# wemos-d1-screw-terminal-v2_0.net
KiCad netlist of a schematic drawn in EAGLE
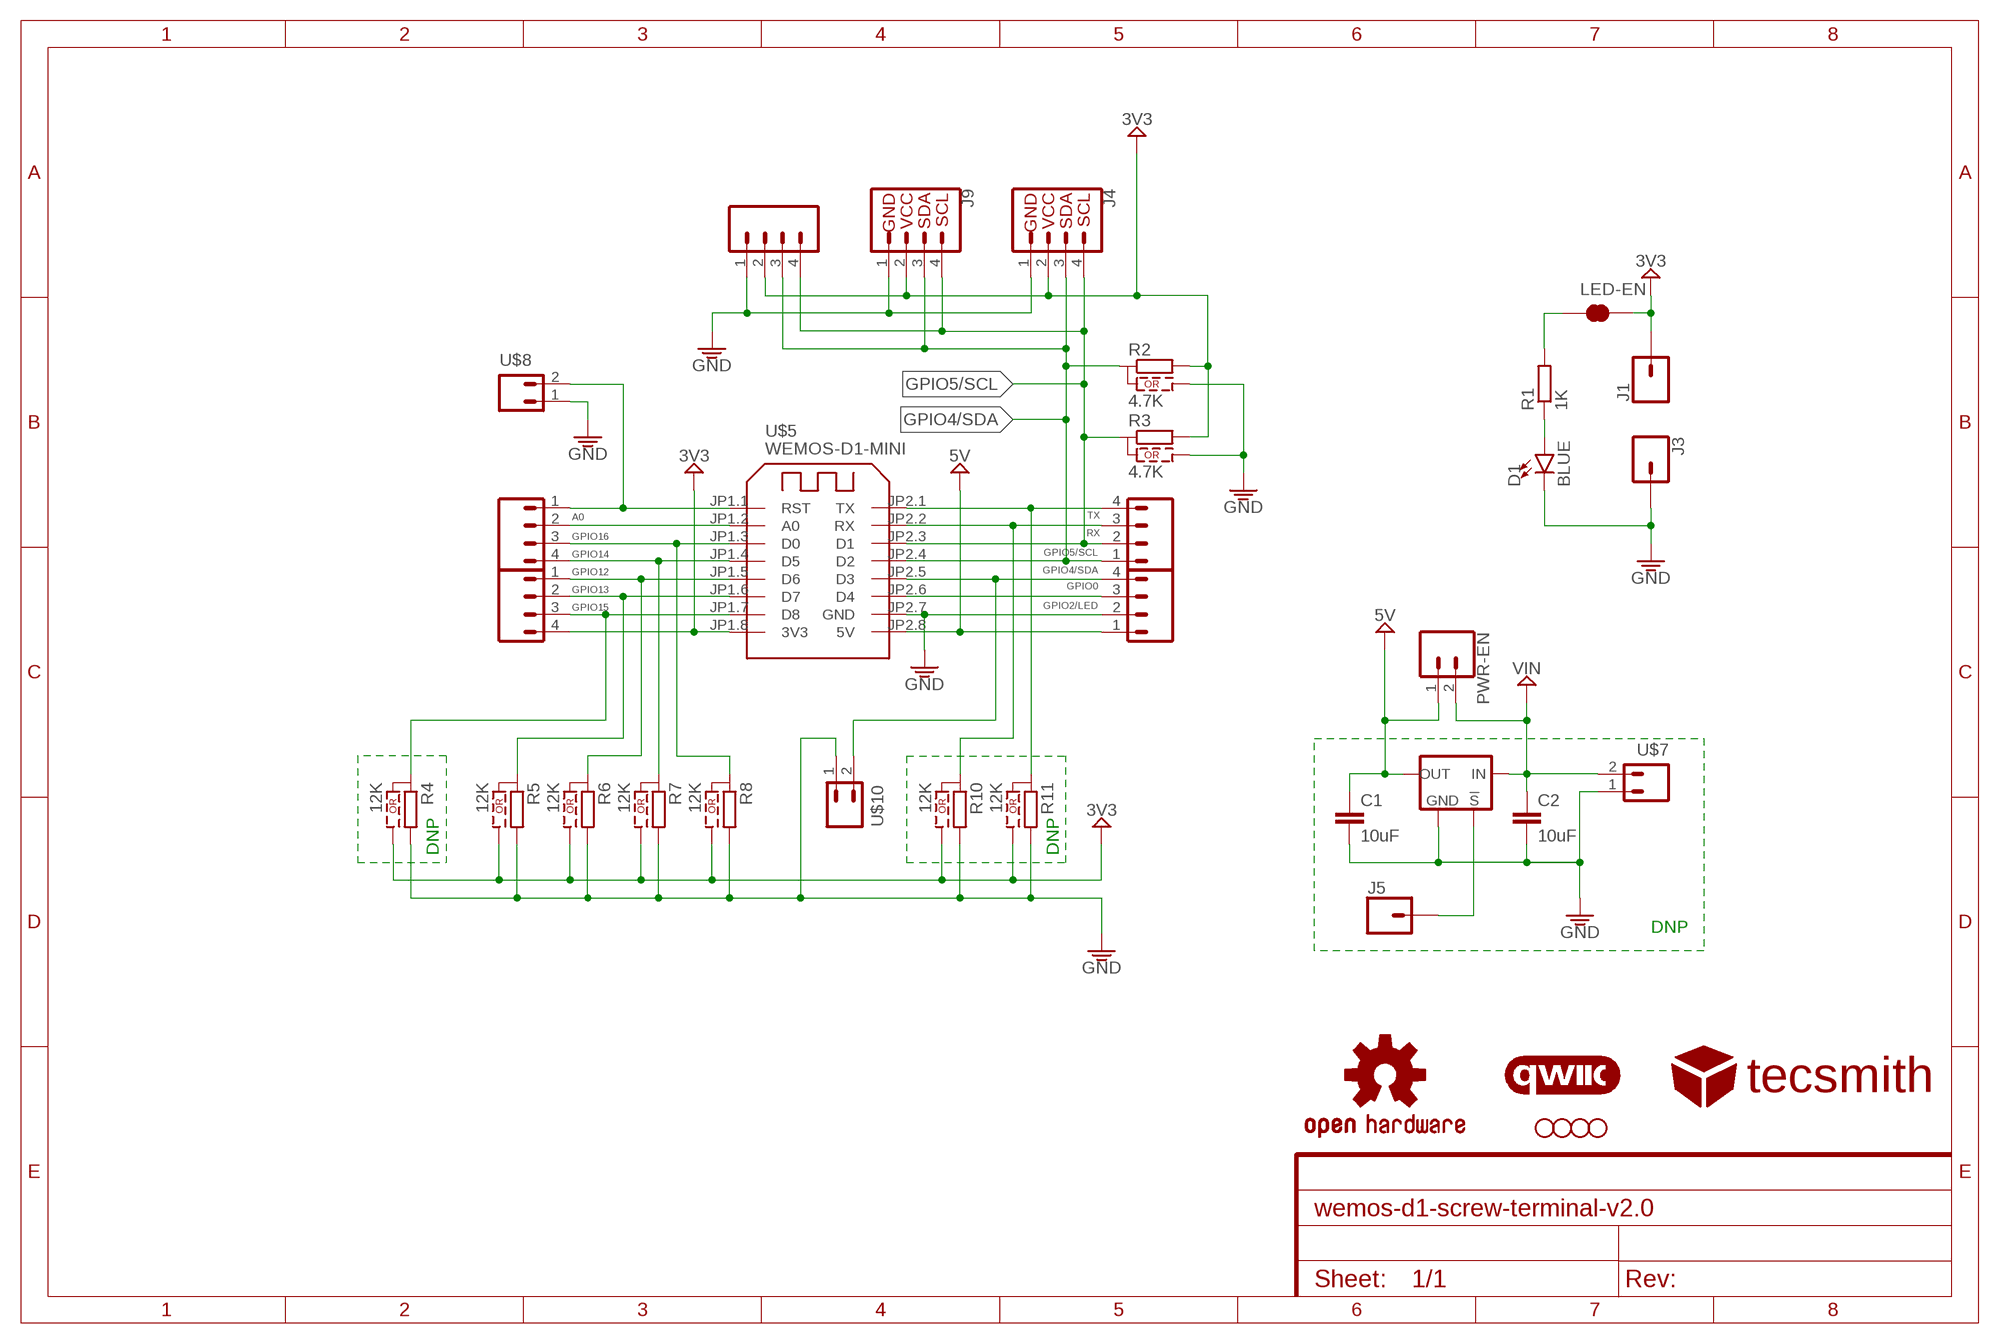
[diagram p0: schematic, sheet 1]

(export (version "E")
  (design (tool "Eeschema 10.0.6"))
  (components
    (comp (ref "C1")
      (value "10uF")
      (footprint "eagle-import:0805")
      (libsource (lib "eagle-import") (part "10UF-0805-10V-10%"))
    )
    (comp (ref "C2")
      (value "10uF")
      (footprint "eagle-import:0805")
      (libsource (lib "eagle-import") (part "10UF-0805-10V-10%"))
    )
    (comp (ref "D1")
      (value "BLUE")
      (footprint "eagle-import:LED-0603")
      (libsource (lib "eagle-import") (part "LED-BLUE0603"))
    )
    (comp (ref "H1")
      (value "STAND-OFF")
      (footprint "eagle-import:STAND-OFF")
      (libsource (lib "eagle-import") (part "STAND-OFF"))
    )
    (comp (ref "H2")
      (value "STAND-OFF")
      (footprint "eagle-import:STAND-OFF")
      (libsource (lib "eagle-import") (part "STAND-OFF"))
    )
    (comp (ref "H5")
      (value "STAND-OFF")
      (footprint "eagle-import:STAND-OFF")
      (libsource (lib "eagle-import") (part "STAND-OFF"))
    )
    (comp (ref "H6")
      (value "STAND-OFF")
      (footprint "eagle-import:STAND-OFF")
      (libsource (lib "eagle-import") (part "STAND-OFF"))
    )
    (comp (ref "J1")
      (value "CONN_01PTH_NO_SILK_YES_STOP")
      (footprint "eagle-import:1X01_NO_SILK")
      (libsource (lib "eagle-import") (part "CONN_01PTH_NO_SILK_YES_STOP"))
    )
    (comp (ref "J2")
      (value "CONN_04PTH")
      (footprint "eagle-import:1X04")
      (libsource (lib "eagle-import") (part "CONN_04PTH"))
    )
    (comp (ref "J3")
      (value "CONN_01PTH_NO_SILK_YES_STOP")
      (footprint "eagle-import:1X01_NO_SILK")
      (libsource (lib "eagle-import") (part "CONN_01PTH_NO_SILK_YES_STOP"))
    )
    (comp (ref "J4")
      (value "QWIIC_RIGHT_ANGLE")
      (footprint "eagle-import:JST04_1MM_RA")
      (libsource (lib "eagle-import") (part "QWIIC_CONNECTORJS-1MM"))
    )
    (comp (ref "J5")
      (value "CONN_01PTH_NO_SILK_YES_STOP")
      (footprint "eagle-import:1X01_NO_SILK")
      (libsource (lib "eagle-import") (part "CONN_01PTH_NO_SILK_YES_STOP"))
    )
    (comp (ref "J9")
      (value "QWIIC_RIGHT_ANGLE")
      (footprint "eagle-import:JST04_1MM_RA")
      (libsource (lib "eagle-import") (part "QWIIC_CONNECTORJS-1MM"))
    )
    (comp (ref "LED-EN")
      (value "JUMPER-SMT_2_NC_TRACE_SILK")
      (footprint "eagle-import:SMT-JUMPER_2_NC_TRACE_SILK")
      (libsource (lib "eagle-import") (part "JUMPER-SMT_2_NC_TRACE_SILK"))
    )
    (comp (ref "LOGO1")
      (value "OSHW-LOGOS")
      (footprint "eagle-import:OSHW-LOGO-S")
      (libsource (lib "eagle-import") (part "OSHW-LOGOS"))
    )
    (comp (ref "LOGO2")
      (value "QWIIC_LOGO_6MM")
      (footprint "eagle-import:QWIIC_6MM")
      (libsource (lib "eagle-import") (part "QWIIC_LOGO_6MM"))
    )
    (comp (ref "PWR-EN")
      (value "CONN_021X02_NO_SILK")
      (footprint "eagle-import:1X02_NO_SILK")
      (libsource (lib "eagle-import") (part "CONN_021X02_NO_SILK"))
    )
    (comp (ref "R1")
      (value "1K")
      (footprint "eagle-import:R0603")
      (libsource (lib "eagle-import") (part "R-EU_R0603"))
    )
    (comp (ref "R2")
      (value "4.7K")
      (footprint "eagle-import:R0603_JMP")
      (libsource (lib "eagle-import") (part "SMT-JUMPER_3_0603"))
    )
    (comp (ref "R3")
      (value "4.7K")
      (footprint "eagle-import:R0603_JMP")
      (libsource (lib "eagle-import") (part "SMT-JUMPER_3_0603"))
    )
    (comp (ref "R4")
      (value "12K")
      (footprint "eagle-import:R0603_JMP")
      (libsource (lib "eagle-import") (part "SMT-JUMPER_3_0603"))
    )
    (comp (ref "R5")
      (value "12K")
      (footprint "eagle-import:R0603_JMP")
      (libsource (lib "eagle-import") (part "SMT-JUMPER_3_0603"))
    )
    (comp (ref "R6")
      (value "12K")
      (footprint "eagle-import:R0603_JMP")
      (libsource (lib "eagle-import") (part "SMT-JUMPER_3_0603"))
    )
    (comp (ref "R7")
      (value "12K")
      (footprint "eagle-import:R0603_JMP")
      (libsource (lib "eagle-import") (part "SMT-JUMPER_3_0603"))
    )
    (comp (ref "R8")
      (value "12K")
      (footprint "eagle-import:R0603_JMP")
      (libsource (lib "eagle-import") (part "SMT-JUMPER_3_0603"))
    )
    (comp (ref "R10")
      (value "12K")
      (footprint "eagle-import:R0603_JMP")
      (libsource (lib "eagle-import") (part "SMT-JUMPER_3_0603"))
    )
    (comp (ref "R11")
      (value "12K")
      (footprint "eagle-import:R0603_JMP")
      (libsource (lib "eagle-import") (part "SMT-JUMPER_3_0603"))
    )
    (comp (ref "U$1")
      (value "CON_04SCREW")
      (footprint "eagle-import:WURTH_2431_3.5MM_4X_SCREW")
      (libsource (lib "eagle-import") (part "CON_04SCREW"))
    )
    (comp (ref "U$2")
      (value "CON_04SCREW")
      (footprint "eagle-import:WURTH_2431_3.5MM_4X_SCREW")
      (libsource (lib "eagle-import") (part "CON_04SCREW"))
    )
    (comp (ref "U$3")
      (value "CON_04SCREW")
      (footprint "eagle-import:WURTH_2431_3.5MM_4X_SCREW")
      (libsource (lib "eagle-import") (part "CON_04SCREW"))
    )
    (comp (ref "U$4")
      (value "CON_04SCREW")
      (footprint "eagle-import:WURTH_2431_3.5MM_4X_SCREW")
      (libsource (lib "eagle-import") (part "CON_04SCREW"))
    )
    (comp (ref "U$5")
      (value "WEMOS-D1-MINI")
      (footprint "eagle-import:WEMOS-D1-MINI")
      (libsource (lib "eagle-import") (part "WEMOS-D1-MINI"))
    )
    (comp (ref "U$6")
      (value "POLOLU-VREG")
      (footprint "eagle-import:TO-220+1")
      (libsource (lib "eagle-import") (part "POLOLU-VREG"))
    )
    (comp (ref "U$7")
      (value "CON_02SCREW")
      (footprint "eagle-import:WURTH_2431_3.5MM_2X_SCREW")
      (libsource (lib "eagle-import") (part "CON_02SCREW"))
    )
    (comp (ref "U$8")
      (value "JST-PH-2")
      (footprint "eagle-import:JST-PH2")
      (libsource (lib "eagle-import") (part "JST-PH-2"))
    )
    (comp (ref "U$9")
      (value "TECSMITH-LOGO")
      (footprint "eagle-import:TECSMITH-LOGO")
      (libsource (lib "eagle-import") (part "TECSMITH-LOGO"))
    )
    (comp (ref "U$10")
      (value "JST-PH-2")
      (footprint "eagle-import:JST-PH2")
      (libsource (lib "eagle-import") (part "JST-PH-2"))
    )
  )
  (nets
    (net (code "1") (name "/A0") (class "Default")
      (node (ref "U$1") (pin "2") (pinfunction "2_2") (pintype "passive"))
      (node (ref "U$5") (pin "JP1.2") (pinfunction "A0_JP1.2") (pintype "bidirectional"))
    )
    (net (code "2") (name "/GPIO0") (class "Default")
      (node (ref "U$10") (pin "2") (pinfunction "2_2") (pintype "passive"))
      (node (ref "U$3") (pin "4") (pinfunction "4_4") (pintype "passive"))
      (node (ref "U$5") (pin "JP2.5") (pinfunction "D3_JP2.5") (pintype "bidirectional"))
    )
    (net (code "3") (name "/GPIO2{slash}LED") (class "Default")
      (node (ref "U$3") (pin "3") (pinfunction "3_3") (pintype "passive"))
      (node (ref "U$5") (pin "JP2.6") (pinfunction "D4_JP2.6") (pintype "bidirectional"))
    )
    (net (code "4") (name "/GPIO12") (class "Default")
      (node (ref "R6") (pin "1") (pinfunction "1_1") (pintype "passive"))
      (node (ref "U$2") (pin "1") (pinfunction "1_1") (pintype "passive"))
      (node (ref "U$5") (pin "JP1.5") (pinfunction "D6_JP1.5") (pintype "bidirectional"))
    )
    (net (code "5") (name "/GPIO13") (class "Default")
      (node (ref "R5") (pin "1") (pinfunction "1_1") (pintype "passive"))
      (node (ref "U$2") (pin "2") (pinfunction "2_2") (pintype "passive"))
      (node (ref "U$5") (pin "JP1.6") (pinfunction "D7_JP1.6") (pintype "bidirectional"))
    )
    (net (code "6") (name "/GPIO14") (class "Default")
      (node (ref "R7") (pin "1") (pinfunction "1_1") (pintype "passive"))
      (node (ref "U$1") (pin "4") (pinfunction "4_4") (pintype "passive"))
      (node (ref "U$5") (pin "JP1.4") (pinfunction "D5_JP1.4") (pintype "bidirectional"))
    )
    (net (code "7") (name "/GPIO15") (class "Default")
      (node (ref "R4") (pin "1") (pinfunction "1_1") (pintype "passive"))
      (node (ref "U$2") (pin "3") (pinfunction "3_3") (pintype "passive"))
      (node (ref "U$5") (pin "JP1.7") (pinfunction "D8_JP1.7") (pintype "bidirectional"))
    )
    (net (code "8") (name "/GPIO16") (class "Default")
      (node (ref "R8") (pin "1") (pinfunction "1_1") (pintype "passive"))
      (node (ref "U$1") (pin "3") (pinfunction "3_3") (pintype "passive"))
      (node (ref "U$5") (pin "JP1.3") (pinfunction "D0_JP1.3") (pintype "bidirectional"))
    )
    (net (code "10") (name "/RX") (class "Default")
      (node (ref "R10") (pin "1") (pinfunction "1_1") (pintype "passive"))
      (node (ref "U$4") (pin "3") (pinfunction "3_3") (pintype "passive"))
      (node (ref "U$5") (pin "JP2.2") (pinfunction "RX_JP2.2") (pintype "bidirectional"))
    )
    (net (code "11") (name "/TX") (class "Default")
      (node (ref "R11") (pin "1") (pinfunction "1_1") (pintype "passive"))
      (node (ref "U$4") (pin "4") (pinfunction "4_4") (pintype "passive"))
      (node (ref "U$5") (pin "JP2.1") (pinfunction "TX_JP2.1") (pintype "bidirectional"))
    )
    (net (code "12") (name "3V3") (class "Default")
      (node (ref "J1") (pin "1") (pinfunction "1_1") (pintype "passive"))
      (node (ref "J2") (pin "2") (pinfunction "2_2") (pintype "passive"))
      (node (ref "J4") (pin "2") (pinfunction "2_2") (pintype "power_in"))
      (node (ref "J9") (pin "2") (pinfunction "2_2") (pintype "power_in"))
      (node (ref "LED-EN") (pin "2") (pinfunction "2_2") (pintype "passive"))
      (node (ref "R10") (pin "3") (pinfunction "3_3") (pintype "passive"))
      (node (ref "R11") (pin "3") (pinfunction "3_3") (pintype "passive"))
      (node (ref "R2") (pin "2") (pinfunction "2_2") (pintype "passive"))
      (node (ref "R3") (pin "2") (pinfunction "2_2") (pintype "passive"))
      (node (ref "R4") (pin "3") (pinfunction "3_3") (pintype "passive"))
      (node (ref "R5") (pin "3") (pinfunction "3_3") (pintype "passive"))
      (node (ref "R6") (pin "3") (pinfunction "3_3") (pintype "passive"))
      (node (ref "R7") (pin "3") (pinfunction "3_3") (pintype "passive"))
      (node (ref "R8") (pin "3") (pinfunction "3_3") (pintype "passive"))
      (node (ref "U$2") (pin "4") (pinfunction "4_4") (pintype "passive"))
      (node (ref "U$5") (pin "JP1.8") (pinfunction "3V3_JP1.8") (pintype "power_in"))
    )
    (net (code "13") (name "5V") (class "Default")
      (node (ref "C1") (pin "1") (pinfunction "1_1") (pintype "passive"))
      (node (ref "PWR-EN") (pin "1") (pinfunction "1_1") (pintype "passive"))
      (node (ref "U$3") (pin "1") (pinfunction "1_1") (pintype "passive"))
      (node (ref "U$5") (pin "JP2.8") (pinfunction "5V_JP2.8") (pintype "power_in"))
      (node (ref "U$6") (pin "OUT") (pinfunction "OUT_OUT") (pintype "output"))
    )
    (net (code "14") (name "GND") (class "Default")
      (node (ref "C1") (pin "2") (pinfunction "2_2") (pintype "passive"))
      (node (ref "C2") (pin "2") (pinfunction "2_2") (pintype "passive"))
      (node (ref "D1") (pin "C") (pinfunction "C_C") (pintype "passive"))
      (node (ref "J2") (pin "1") (pinfunction "1_1") (pintype "passive"))
      (node (ref "J3") (pin "1") (pinfunction "1_1") (pintype "passive"))
      (node (ref "J4") (pin "1") (pinfunction "1_1") (pintype "power_in"))
      (node (ref "J9") (pin "1") (pinfunction "1_1") (pintype "power_in"))
      (node (ref "R10") (pin "2") (pinfunction "2_2") (pintype "passive"))
      (node (ref "R11") (pin "2") (pinfunction "2_2") (pintype "passive"))
      (node (ref "R2") (pin "3") (pinfunction "3_3") (pintype "passive"))
      (node (ref "R3") (pin "3") (pinfunction "3_3") (pintype "passive"))
      (node (ref "R4") (pin "2") (pinfunction "2_2") (pintype "passive"))
      (node (ref "R5") (pin "2") (pinfunction "2_2") (pintype "passive"))
      (node (ref "R6") (pin "2") (pinfunction "2_2") (pintype "passive"))
      (node (ref "R7") (pin "2") (pinfunction "2_2") (pintype "passive"))
      (node (ref "R8") (pin "2") (pinfunction "2_2") (pintype "passive"))
      (node (ref "U$10") (pin "1") (pinfunction "1_1") (pintype "passive"))
      (node (ref "U$3") (pin "2") (pinfunction "2_2") (pintype "passive"))
      (node (ref "U$5") (pin "JP2.7") (pinfunction "GND_JP2.7") (pintype "power_in"))
      (node (ref "U$6") (pin "GND") (pinfunction "GND_GND") (pintype "power_in"))
      (node (ref "U$7") (pin "1") (pinfunction "1_1") (pintype "passive"))
      (node (ref "U$8") (pin "1") (pinfunction "1_1") (pintype "passive"))
    )
    (net (code "15") (name "GPIO4{slash}SDA") (class "Default")
      (node (ref "J2") (pin "3") (pinfunction "3_3") (pintype "passive"))
      (node (ref "J4") (pin "3") (pinfunction "3_3") (pintype "passive"))
      (node (ref "J9") (pin "3") (pinfunction "3_3") (pintype "passive"))
      (node (ref "R2") (pin "1") (pinfunction "1_1") (pintype "passive"))
      (node (ref "U$4") (pin "1") (pinfunction "1_1") (pintype "passive"))
      (node (ref "U$5") (pin "JP2.4") (pinfunction "D2_JP2.4") (pintype "bidirectional"))
    )
    (net (code "16") (name "GPIO5{slash}SCL") (class "Default")
      (node (ref "J2") (pin "4") (pinfunction "4_4") (pintype "passive"))
      (node (ref "J4") (pin "4") (pinfunction "4_4") (pintype "passive"))
      (node (ref "J9") (pin "4") (pinfunction "4_4") (pintype "passive"))
      (node (ref "R3") (pin "1") (pinfunction "1_1") (pintype "passive"))
      (node (ref "U$4") (pin "2") (pinfunction "2_2") (pintype "passive"))
      (node (ref "U$5") (pin "JP2.3") (pinfunction "D1_JP2.3") (pintype "bidirectional"))
    )
    (net (code "17") (name "Net-(D1-PadA)") (class "Default")
      (node (ref "D1") (pin "A") (pinfunction "A_A") (pintype "passive"))
      (node (ref "R1") (pin "1") (pinfunction "1_1") (pintype "passive"))
    )
    (net (code "18") (name "Net-(LED-EN-Pad1)") (class "Default")
      (node (ref "LED-EN") (pin "1") (pinfunction "1_1") (pintype "passive"))
      (node (ref "R1") (pin "2") (pinfunction "2_2") (pintype "passive"))
    )
    (net (code "19") (name "Net-(U$5-RST)") (class "Default")
      (node (ref "U$1") (pin "1") (pinfunction "1_1") (pintype "passive"))
      (node (ref "U$5") (pin "JP1.1") (pinfunction "RST_JP1.1") (pintype "bidirectional"))
      (node (ref "U$8") (pin "2") (pinfunction "2_2") (pintype "passive"))
    )
    (net (code "20") (name "Net-(U$6-~{SHDN})") (class "Default")
      (node (ref "J5") (pin "1") (pinfunction "1_1") (pintype "passive"))
      (node (ref "U$6") (pin "!SHDN") (pinfunction "~{SHDN}_!SHDN") (pintype "bidirectional"))
    )
    (net (code "21") (name "VIN") (class "Default")
      (node (ref "C2") (pin "1") (pinfunction "1_1") (pintype "passive"))
      (node (ref "PWR-EN") (pin "2") (pinfunction "2_2") (pintype "passive"))
      (node (ref "U$6") (pin "IN") (pinfunction "IN_IN") (pintype "input"))
      (node (ref "U$7") (pin "2") (pinfunction "2_2") (pintype "passive"))
    )
  )
)
